# schematic.net
KiCad netlist of a schematic drawn in Altium Designer
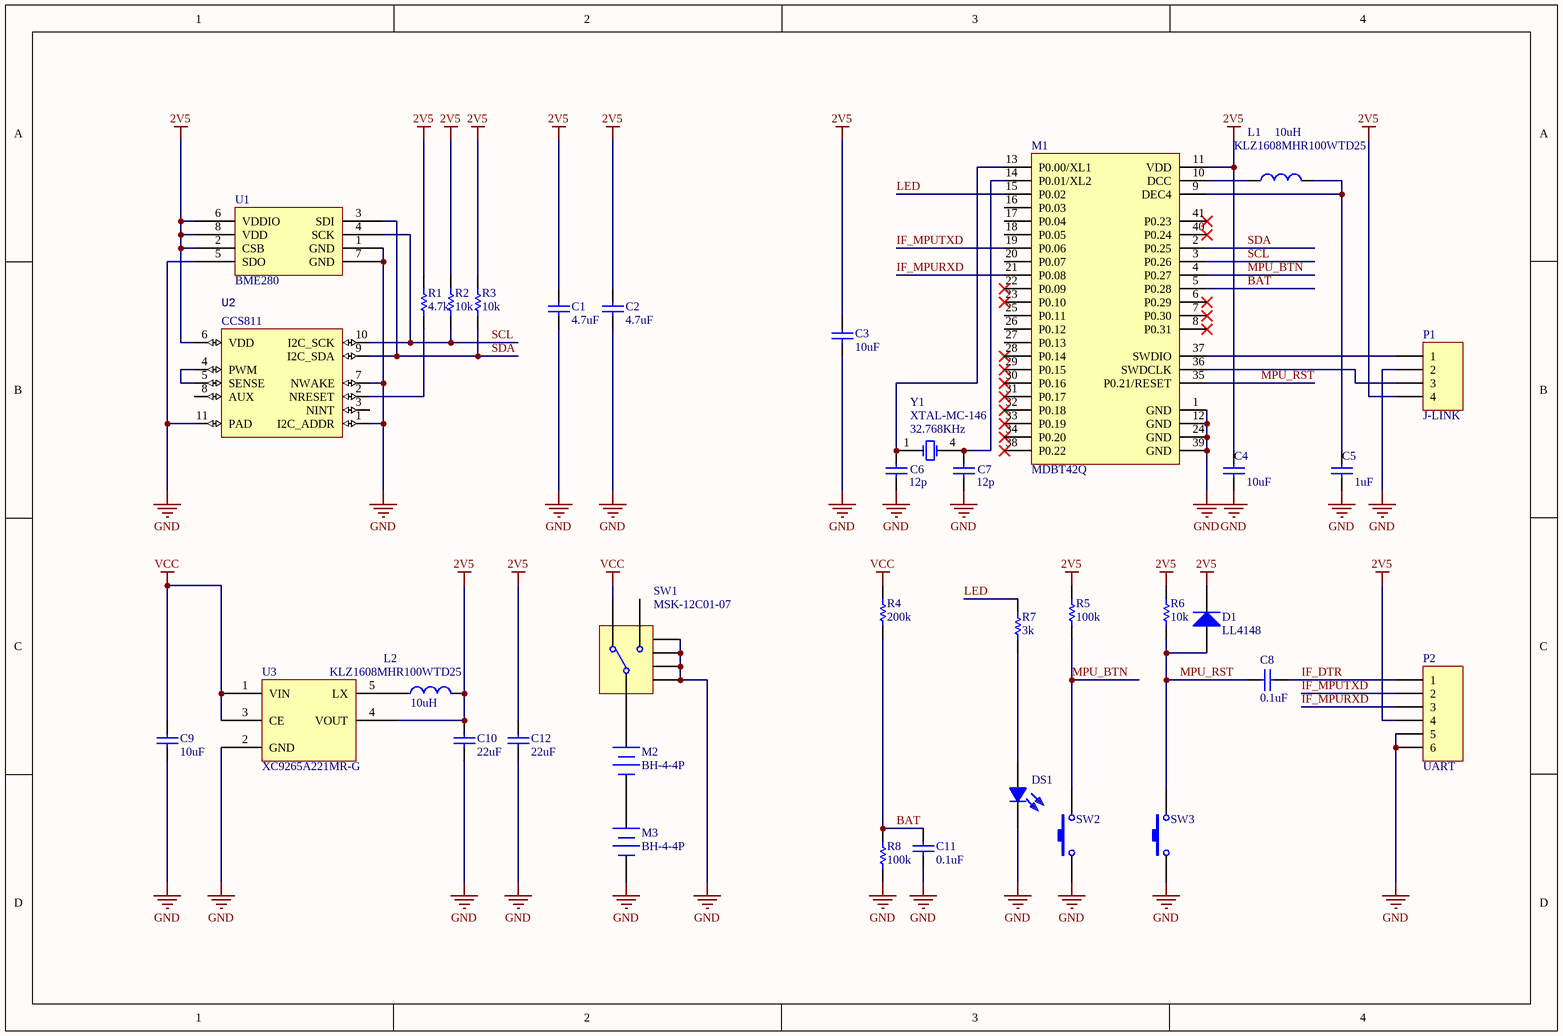
[diagram p0: schematic.SchDoc]

(export (version "E")
  (design (tool "Eeschema 10.0.6"))
  (components
    (comp (ref "C1")
      (value "4.7uF")
      (footprint "1608[0603]")
      (fields (field (name "Comment") "Cap1"))
      (libsource (lib "Other") (part "Cap1"))
    )
    (comp (ref "C2")
      (value "4.7uF")
      (footprint "1608[0603]")
      (fields (field (name "Comment") "Cap1"))
      (libsource (lib "Other") (part "Cap1"))
    )
    (comp (ref "C3")
      (value "10uF")
      (footprint "1608[0603]")
      (fields (field (name "Comment") "Cap1"))
      (libsource (lib "Other") (part "Cap1"))
    )
    (comp (ref "C4")
      (value "10uF")
      (footprint "2012[0805]")
      (fields (field (name "Comment") "Cap1"))
      (libsource (lib "Other") (part "Cap1"))
    )
    (comp (ref "C5")
      (value "1uF")
      (footprint "1608[0603]")
      (fields (field (name "Comment") "Cap1"))
      (libsource (lib "Other") (part "Cap1"))
    )
    (comp (ref "C6")
      (value "12p")
      (footprint "1608[0603]")
      (fields (field (name "Comment") "Cap1"))
      (libsource (lib "Other") (part "Cap1"))
    )
    (comp (ref "C7")
      (value "12p")
      (footprint "1608[0603]")
      (fields (field (name "Comment") "Cap1"))
      (libsource (lib "Other") (part "Cap1"))
    )
    (comp (ref "C8")
      (value "0.1uF")
      (footprint "1608[0603]")
      (fields (field (name "Comment") "Cap1"))
      (libsource (lib "Other") (part "Cap1"))
    )
    (comp (ref "C9")
      (value "10uF")
      (footprint "Land2.54-2")
      (fields (field (name "Comment") "Cap1"))
      (libsource (lib "Other") (part "Cap1"))
    )
    (comp (ref "C10")
      (value "22uF")
      (footprint "Land2.54-2")
      (fields (field (name "Comment") "Cap1"))
      (libsource (lib "Other") (part "Cap1"))
    )
    (comp (ref "C11")
      (value "0.1uF")
      (footprint "1608[0603]")
      (fields (field (name "Comment") "Cap1"))
      (libsource (lib "Other") (part "Cap1"))
    )
    (comp (ref "C12")
      (value "22uF")
      (footprint "Land2.54-2")
      (fields (field (name "Comment") "Cap1"))
      (libsource (lib "Other") (part "Cap1"))
    )
    (comp (ref "D1") (value "LL4148") (footprint "SOD80") (libsource (lib "Diode") (part "LL4148")))
    (comp (ref "DS1") (value "~") (footprint "3216[1206]+A") (libsource (lib "Optical") (part "LED")))
    (comp (ref "L1")
      (value "KLZ1608MHR100WTD25")
      (footprint "2012[0805]")
      (fields (field (name "ALTIUM_VALUE") "10uH"))
      (libsource (lib "Other") (part "Inductor"))
    )
    (comp (ref "L2")
      (value "KLZ1608MHR100WTD25")
      (footprint "2012[0805]")
      (description "1239AS-H-100M")
      (fields (field (name "ALTIUM_VALUE") "10uH"))
      (libsource (lib "Other") (part "Inductor"))
    )
    (comp (ref "M1") (value "MDBT42Q") (footprint "MDBT42Q") (libsource (lib "Module") (part "MDBT42Q")))
    (comp (ref "M2") (value "BH-4-4P") (footprint "BH-4-4P") (libsource (lib "newlib") (part "BH-4-4P")))
    (comp (ref "M3") (value "BH-4-4P") (footprint "BH-4-4P") (libsource (lib "newlib") (part "BH-4-4P")))
    (comp (ref "P1")
      (value "J-LINK")
      (footprint "HDR1X4")
      (description "Header, 4-Pin")
      (fields (field (name "PUBLISHER") "Altium Limited"))
      (libsource (lib "Connector") (part "Header 4"))
    )
    (comp (ref "P2")
      (value "UART")
      (footprint "HDR1X6")
      (description "Header, 6-Pin")
      (fields (field (name "PUBLISHER") "Altium Limited"))
      (libsource (lib "Connector") (part "Header 6"))
    )
    (comp (ref "R1")
      (value "4.7k")
      (footprint "1608[0603]")
      (fields (field (name "Comment") "Res"))
      (libsource (lib "Other") (part "Res"))
    )
    (comp (ref "R2")
      (value "10k")
      (footprint "1608[0603]")
      (fields (field (name "Comment") "Res"))
      (libsource (lib "Other") (part "Res"))
    )
    (comp (ref "R3")
      (value "10k")
      (footprint "1608[0603]")
      (fields (field (name "Comment") "Res"))
      (libsource (lib "Other") (part "Res"))
    )
    (comp (ref "R4")
      (value "200k")
      (footprint "1608[0603]")
      (fields (field (name "Comment") "Res"))
      (libsource (lib "Other") (part "Res"))
    )
    (comp (ref "R5")
      (value "100k")
      (footprint "1608[0603]")
      (fields (field (name "Comment") "Res"))
      (libsource (lib "Other") (part "Res"))
    )
    (comp (ref "R6")
      (value "10k")
      (footprint "1608[0603]")
      (fields (field (name "Comment") "Res"))
      (libsource (lib "Other") (part "Res"))
    )
    (comp (ref "R7")
      (value "3k")
      (footprint "1608[0603]")
      (fields (field (name "Comment") "Res"))
      (libsource (lib "Other") (part "Res"))
    )
    (comp (ref "R8")
      (value "100k")
      (footprint "1608[0603]")
      (fields (field (name "Comment") "Res"))
      (libsource (lib "Other") (part "Res"))
    )
    (comp (ref "SW1")
      (value "MSK-12C01-07")
      (footprint "MSK-12C01-07")
      (libsource (lib "Switch") (part "MSK-12C01-07"))
    )
    (comp (ref "SW2")
      (value "TL3342F160QG")
      (footprint "TL3342F160QG")
      (libsource (lib "Switch") (part "TL3342F160QG"))
    )
    (comp (ref "SW3")
      (value "TL3342F160QG")
      (footprint "TL3342F160QG")
      (libsource (lib "Switch") (part "TL3342F160QG"))
    )
    (comp (ref "U1") (value "BME280") (footprint "BME280") (libsource (lib "newlib") (part "BME280")))
    (comp (ref "U2")
      (value "CCS811")
      (footprint "LGA-10")
      (fields (field (name "DEVICESETNAME") "CCS811") (field (name "MOUSER_PART_NUMBER") "985-CCS811"))
      (libsource (lib "newlib") (part "CCS811"))
    )
    (comp (ref "U3") (value "XC9265A221MR-G") (libsource (lib "newlib") (part "XC9265A221MR-G")))
    (comp (ref "Y1")
      (value "XTAL-MC-146")
      (footprint "MC-146")
      (fields (field (name "ALTIUM_VALUE") "32.768KHz"))
      (libsource (lib "Signal") (part "XTAL-MC-146"))
    )
  )
  (nets
    (net (code "1") (name "/BAT") (class "Default")
      (node (ref "C11") (pin "1") (pinfunction "1_1") (pintype "passive"))
      (node (ref "M1") (pin "5") (pinfunction "P0.28_5") (pintype "passive"))
      (node (ref "R4") (pin "2") (pinfunction "2_2") (pintype "passive"))
      (node (ref "R8") (pin "1") (pinfunction "1_1") (pintype "passive"))
    )
    (net (code "2") (name "/IF_DTR") (class "Default")
      (node (ref "C8") (pin "1") (pinfunction "1_1") (pintype "passive"))
      (node (ref "P2") (pin "1") (pinfunction "1_1") (pintype "passive"))
    )
    (net (code "3") (name "/IF_MPURXD") (class "Default")
      (node (ref "M1") (pin "21") (pinfunction "P0.08_21") (pintype "passive"))
      (node (ref "P2") (pin "3") (pinfunction "3_3") (pintype "passive"))
    )
    (net (code "4") (name "/IF_MPUTXD") (class "Default")
      (node (ref "M1") (pin "19") (pinfunction "P0.06_19") (pintype "passive"))
      (node (ref "P2") (pin "2") (pinfunction "2_2") (pintype "passive"))
    )
    (net (code "5") (name "/LED") (class "Default")
      (node (ref "M1") (pin "15") (pinfunction "P0.02_15") (pintype "passive"))
      (node (ref "R7") (pin "1") (pinfunction "1_1") (pintype "passive"))
    )
    (net (code "6") (name "/MPU_BTN") (class "Default")
      (node (ref "M1") (pin "4") (pinfunction "P0.27_4") (pintype "passive"))
      (node (ref "R5") (pin "2") (pinfunction "2_2") (pintype "passive"))
      (node (ref "SW2") (pin "3") (pinfunction "3_3") (pintype "passive"))
    )
    (net (code "7") (name "/MPU_RST") (class "Default")
      (node (ref "C8") (pin "2") (pinfunction "2_2") (pintype "passive"))
      (node (ref "D1") (pin "1") (pinfunction "A_1") (pintype "passive"))
      (node (ref "M1") (pin "35") (pinfunction "P0.21/RESET_35") (pintype "passive"))
      (node (ref "R6") (pin "2") (pinfunction "2_2") (pintype "passive"))
      (node (ref "SW3") (pin "3") (pinfunction "3_3") (pintype "passive"))
    )
    (net (code "8") (name "/SCL") (class "Default")
      (node (ref "M1") (pin "3") (pinfunction "P0.26_3") (pintype "passive"))
      (node (ref "R2") (pin "2") (pinfunction "2_2") (pintype "passive"))
      (node (ref "U1") (pin "4") (pinfunction "SCK_4") (pintype "passive"))
      (node (ref "U2") (pin "10") (pinfunction "I2C_SCK_10") (pintype "bidirectional"))
    )
    (net (code "9") (name "/SDA") (class "Default")
      (node (ref "M1") (pin "2") (pinfunction "P0.25_2") (pintype "passive"))
      (node (ref "R3") (pin "2") (pinfunction "2_2") (pintype "passive"))
      (node (ref "U1") (pin "3") (pinfunction "SDI_3") (pintype "passive"))
      (node (ref "U2") (pin "9") (pinfunction "I2C_SDA_9") (pintype "bidirectional"))
    )
    (net (code "10") (name "2V5") (class "Default")
      (node (ref "C1") (pin "1") (pinfunction "1_1") (pintype "passive"))
      (node (ref "C10") (pin "2") (pinfunction "2_2") (pintype "passive"))
      (node (ref "C12") (pin "2") (pinfunction "2_2") (pintype "passive"))
      (node (ref "C2") (pin "1") (pinfunction "1_1") (pintype "passive"))
      (node (ref "C3") (pin "1") (pinfunction "1_1") (pintype "passive"))
      (node (ref "C4") (pin "2") (pinfunction "2_2") (pintype "passive"))
      (node (ref "D1") (pin "2") (pinfunction "K_2") (pintype "passive"))
      (node (ref "L2") (pin "2") (pinfunction "2_2") (pintype "passive"))
      (node (ref "M1") (pin "11") (pinfunction "VDD_11") (pintype "passive"))
      (node (ref "P1") (pin "4") (pinfunction "4_4") (pintype "passive"))
      (node (ref "P2") (pin "4") (pinfunction "4_4") (pintype "passive"))
      (node (ref "R1") (pin "1") (pinfunction "1_1") (pintype "passive"))
      (node (ref "R2") (pin "1") (pinfunction "1_1") (pintype "passive"))
      (node (ref "R3") (pin "1") (pinfunction "1_1") (pintype "passive"))
      (node (ref "R5") (pin "1") (pinfunction "1_1") (pintype "passive"))
      (node (ref "R6") (pin "1") (pinfunction "1_1") (pintype "passive"))
      (node (ref "U1") (pin "2") (pinfunction "CSB_2") (pintype "passive"))
      (node (ref "U1") (pin "6") (pinfunction "VDDIO_6") (pintype "passive"))
      (node (ref "U1") (pin "8") (pinfunction "VDD_8") (pintype "passive"))
      (node (ref "U2") (pin "6") (pinfunction "VDD_6") (pintype "bidirectional"))
      (node (ref "U3") (pin "4") (pinfunction "VOUT_4") (pintype "passive"))
    )
    (net (code "11") (name "GND") (class "Default")
      (node (ref "C1") (pin "2") (pinfunction "2_2") (pintype "passive"))
      (node (ref "C10") (pin "1") (pinfunction "1_1") (pintype "passive"))
      (node (ref "C11") (pin "2") (pinfunction "2_2") (pintype "passive"))
      (node (ref "C12") (pin "1") (pinfunction "1_1") (pintype "passive"))
      (node (ref "C2") (pin "2") (pinfunction "2_2") (pintype "passive"))
      (node (ref "C3") (pin "2") (pinfunction "2_2") (pintype "passive"))
      (node (ref "C4") (pin "1") (pinfunction "1_1") (pintype "passive"))
      (node (ref "C5") (pin "1") (pinfunction "1_1") (pintype "passive"))
      (node (ref "C6") (pin "1") (pinfunction "1_1") (pintype "passive"))
      (node (ref "C7") (pin "1") (pinfunction "1_1") (pintype "passive"))
      (node (ref "C9") (pin "1") (pinfunction "1_1") (pintype "passive"))
      (node (ref "DS1") (pin "2") (pintype "passive"))
      (node (ref "M1") (pin "1") (pinfunction "GND_1") (pintype "passive"))
      (node (ref "M1") (pin "12") (pinfunction "GND_12") (pintype "passive"))
      (node (ref "M1") (pin "24") (pinfunction "GND_24") (pintype "passive"))
      (node (ref "M1") (pin "39") (pinfunction "GND_39") (pintype "passive"))
      (node (ref "M3") (pin "2") (pinfunction "-_2") (pintype "passive"))
      (node (ref "P1") (pin "2") (pinfunction "2_2") (pintype "passive"))
      (node (ref "P2") (pin "5") (pinfunction "5_5") (pintype "passive"))
      (node (ref "P2") (pin "6") (pinfunction "6_6") (pintype "passive"))
      (node (ref "R8") (pin "2") (pinfunction "2_2") (pintype "passive"))
      (node (ref "SW1") (pin "4") (pinfunction "4_4") (pintype "passive"))
      (node (ref "SW1") (pin "5") (pinfunction "5_5") (pintype "passive"))
      (node (ref "SW1") (pin "6") (pinfunction "6_6") (pintype "passive"))
      (node (ref "SW1") (pin "7") (pinfunction "7_7") (pintype "passive"))
      (node (ref "SW2") (pin "1") (pinfunction "1_1") (pintype "passive"))
      (node (ref "SW3") (pin "1") (pinfunction "1_1") (pintype "passive"))
      (node (ref "U1") (pin "1") (pinfunction "GND_1") (pintype "passive"))
      (node (ref "U1") (pin "5") (pinfunction "SDO_5") (pintype "passive"))
      (node (ref "U1") (pin "7") (pinfunction "GND_7") (pintype "passive"))
      (node (ref "U2") (pin "1") (pinfunction "I2C_ADDR_1") (pintype "bidirectional"))
      (node (ref "U2") (pin "11") (pinfunction "PAD_11") (pintype "bidirectional"))
      (node (ref "U2") (pin "7") (pinfunction "NWAKE_7") (pintype "bidirectional"))
      (node (ref "U3") (pin "2") (pinfunction "GND_2") (pintype "passive"))
    )
    (net (code "12") (name "Net-(DS1-Pad1)") (class "Default")
      (node (ref "DS1") (pin "1") (pintype "passive"))
      (node (ref "R7") (pin "2") (pinfunction "2_2") (pintype "passive"))
    )
    (net (code "13") (name "Net-(M1-DCC)") (class "Default")
      (node (ref "L1") (pin "1") (pinfunction "1_1") (pintype "passive"))
      (node (ref "M1") (pin "10") (pinfunction "DCC_10") (pintype "passive"))
    )
    (net (code "14") (name "Net-(M1-DEC4)") (class "Default")
      (node (ref "C5") (pin "2") (pinfunction "2_2") (pintype "passive"))
      (node (ref "L1") (pin "2") (pinfunction "2_2") (pintype "passive"))
      (node (ref "M1") (pin "9") (pinfunction "DEC4_9") (pintype "passive"))
    )
    (net (code "15") (name "Net-(M1-P0.00{slash}XL1)") (class "Default")
      (node (ref "C6") (pin "2") (pinfunction "2_2") (pintype "passive"))
      (node (ref "M1") (pin "13") (pinfunction "P0.00/XL1_13") (pintype "passive"))
      (node (ref "Y1") (pin "1") (pinfunction "OSC1_1") (pintype "passive"))
    )
    (net (code "16") (name "Net-(M1-P0.01{slash}XL2)") (class "Default")
      (node (ref "C7") (pin "2") (pinfunction "2_2") (pintype "passive"))
      (node (ref "M1") (pin "14") (pinfunction "P0.01/XL2_14") (pintype "passive"))
      (node (ref "Y1") (pin "4") (pinfunction "OSC2_4") (pintype "passive"))
    )
    (net (code "17") (name "Net-(M1-SWDCLK)") (class "Default")
      (node (ref "M1") (pin "36") (pinfunction "SWDCLK_36") (pintype "passive"))
      (node (ref "P1") (pin "3") (pinfunction "3_3") (pintype "passive"))
    )
    (net (code "18") (name "Net-(M1-SWDIO)") (class "Default")
      (node (ref "M1") (pin "37") (pinfunction "SWDIO_37") (pintype "passive"))
      (node (ref "P1") (pin "1") (pinfunction "1_1") (pintype "passive"))
    )
    (net (code "19") (name "Net-(M2-+)") (class "Default")
      (node (ref "M2") (pin "1") (pinfunction "+_1") (pintype "passive"))
      (node (ref "SW1") (pin "2") (pinfunction "2_2") (pintype "passive"))
    )
    (net (code "20") (name "Net-(M2--)") (class "Default")
      (node (ref "M2") (pin "2") (pinfunction "-_2") (pintype "passive"))
      (node (ref "M3") (pin "1") (pinfunction "+_1") (pintype "passive"))
    )
    (net (code "21") (name "Net-(U2-NRESET)") (class "Default")
      (node (ref "R1") (pin "2") (pinfunction "2_2") (pintype "passive"))
      (node (ref "U2") (pin "2") (pinfunction "NRESET_2") (pintype "bidirectional"))
    )
    (net (code "22") (name "Net-(U2-PWM)") (class "Default")
      (node (ref "U2") (pin "4") (pinfunction "PWM_4") (pintype "bidirectional"))
      (node (ref "U2") (pin "5") (pinfunction "SENSE_5") (pintype "bidirectional"))
    )
    (net (code "23") (name "Net-(U3-LX)") (class "Default")
      (node (ref "L2") (pin "1") (pinfunction "1_1") (pintype "passive"))
      (node (ref "U3") (pin "5") (pinfunction "LX_5") (pintype "passive"))
    )
    (net (code "24") (name "VCC") (class "Default")
      (node (ref "C9") (pin "2") (pinfunction "2_2") (pintype "passive"))
      (node (ref "R4") (pin "1") (pinfunction "1_1") (pintype "passive"))
      (node (ref "SW1") (pin "1") (pinfunction "1_1") (pintype "passive"))
      (node (ref "U3") (pin "1") (pinfunction "VIN_1") (pintype "passive"))
      (node (ref "U3") (pin "3") (pinfunction "CE_3") (pintype "passive"))
    )
    (net (code "25") (name "unconnected-(M1-P0.03-Pad16)") (class "Default")
      (node (ref "M1") (pin "16") (pinfunction "P0.03_16") (pintype "passive"))
    )
    (net (code "26") (name "unconnected-(M1-P0.04-Pad17)") (class "Default")
      (node (ref "M1") (pin "17") (pinfunction "P0.04_17") (pintype "passive"))
    )
    (net (code "27") (name "unconnected-(M1-P0.05-Pad18)") (class "Default")
      (node (ref "M1") (pin "18") (pinfunction "P0.05_18") (pintype "passive"))
    )
    (net (code "28") (name "unconnected-(M1-P0.07-Pad20)") (class "Default")
      (node (ref "M1") (pin "20") (pinfunction "P0.07_20") (pintype "passive"))
    )
    (net (code "29") (name "unconnected-(M1-P0.09-Pad22)") (class "Default")
      (node (ref "M1") (pin "22") (pinfunction "P0.09_22") (pintype "passive+no_connect"))
    )
    (net (code "30") (name "unconnected-(M1-P0.10-Pad23)") (class "Default")
      (node (ref "M1") (pin "23") (pinfunction "P0.10_23") (pintype "passive+no_connect"))
    )
    (net (code "31") (name "unconnected-(M1-P0.11-Pad25)") (class "Default")
      (node (ref "M1") (pin "25") (pinfunction "P0.11_25") (pintype "passive"))
    )
    (net (code "32") (name "unconnected-(M1-P0.12-Pad26)") (class "Default")
      (node (ref "M1") (pin "26") (pinfunction "P0.12_26") (pintype "passive"))
    )
    (net (code "33") (name "unconnected-(M1-P0.13-Pad27)") (class "Default")
      (node (ref "M1") (pin "27") (pinfunction "P0.13_27") (pintype "passive"))
    )
    (net (code "34") (name "unconnected-(M1-P0.14-Pad28)") (class "Default")
      (node (ref "M1") (pin "28") (pinfunction "P0.14_28") (pintype "passive+no_connect"))
    )
    (net (code "35") (name "unconnected-(M1-P0.15-Pad29)") (class "Default")
      (node (ref "M1") (pin "29") (pinfunction "P0.15_29") (pintype "passive+no_connect"))
    )
    (net (code "36") (name "unconnected-(M1-P0.16-Pad30)") (class "Default")
      (node (ref "M1") (pin "30") (pinfunction "P0.16_30") (pintype "passive+no_connect"))
    )
    (net (code "37") (name "unconnected-(M1-P0.17-Pad31)") (class "Default")
      (node (ref "M1") (pin "31") (pinfunction "P0.17_31") (pintype "passive+no_connect"))
    )
    (net (code "38") (name "unconnected-(M1-P0.18-Pad32)") (class "Default")
      (node (ref "M1") (pin "32") (pinfunction "P0.18_32") (pintype "passive+no_connect"))
    )
    (net (code "39") (name "unconnected-(M1-P0.19-Pad33)") (class "Default")
      (node (ref "M1") (pin "33") (pinfunction "P0.19_33") (pintype "passive+no_connect"))
    )
    (net (code "40") (name "unconnected-(M1-P0.20-Pad34)") (class "Default")
      (node (ref "M1") (pin "34") (pinfunction "P0.20_34") (pintype "passive+no_connect"))
    )
    (net (code "41") (name "unconnected-(M1-P0.22-Pad38)") (class "Default")
      (node (ref "M1") (pin "38") (pinfunction "P0.22_38") (pintype "passive+no_connect"))
    )
    (net (code "42") (name "unconnected-(M1-P0.23-Pad41)") (class "Default")
      (node (ref "M1") (pin "41") (pinfunction "P0.23_41") (pintype "passive+no_connect"))
    )
    (net (code "43") (name "unconnected-(M1-P0.24-Pad40)") (class "Default")
      (node (ref "M1") (pin "40") (pinfunction "P0.24_40") (pintype "passive+no_connect"))
    )
    (net (code "44") (name "unconnected-(M1-P0.29-Pad6)") (class "Default")
      (node (ref "M1") (pin "6") (pinfunction "P0.29_6") (pintype "passive+no_connect"))
    )
    (net (code "45") (name "unconnected-(M1-P0.30-Pad7)") (class "Default")
      (node (ref "M1") (pin "7") (pinfunction "P0.30_7") (pintype "passive+no_connect"))
    )
    (net (code "46") (name "unconnected-(M1-P0.31-Pad8)") (class "Default")
      (node (ref "M1") (pin "8") (pinfunction "P0.31_8") (pintype "passive+no_connect"))
    )
    (net (code "47") (name "unconnected-(SW1-Pad3)") (class "Default")
      (node (ref "SW1") (pin "3") (pinfunction "3_3") (pintype "passive"))
    )
    (net (code "48") (name "unconnected-(U2-AUX-Pad8)") (class "Default")
      (node (ref "U2") (pin "8") (pinfunction "AUX_8") (pintype "bidirectional"))
    )
    (net (code "49") (name "unconnected-(U2-NINT-Pad3)") (class "Default")
      (node (ref "U2") (pin "3") (pinfunction "NINT_3") (pintype "bidirectional"))
    )
  )
)
